# main.net
KiCad netlist of a schematic drawn in EAGLE
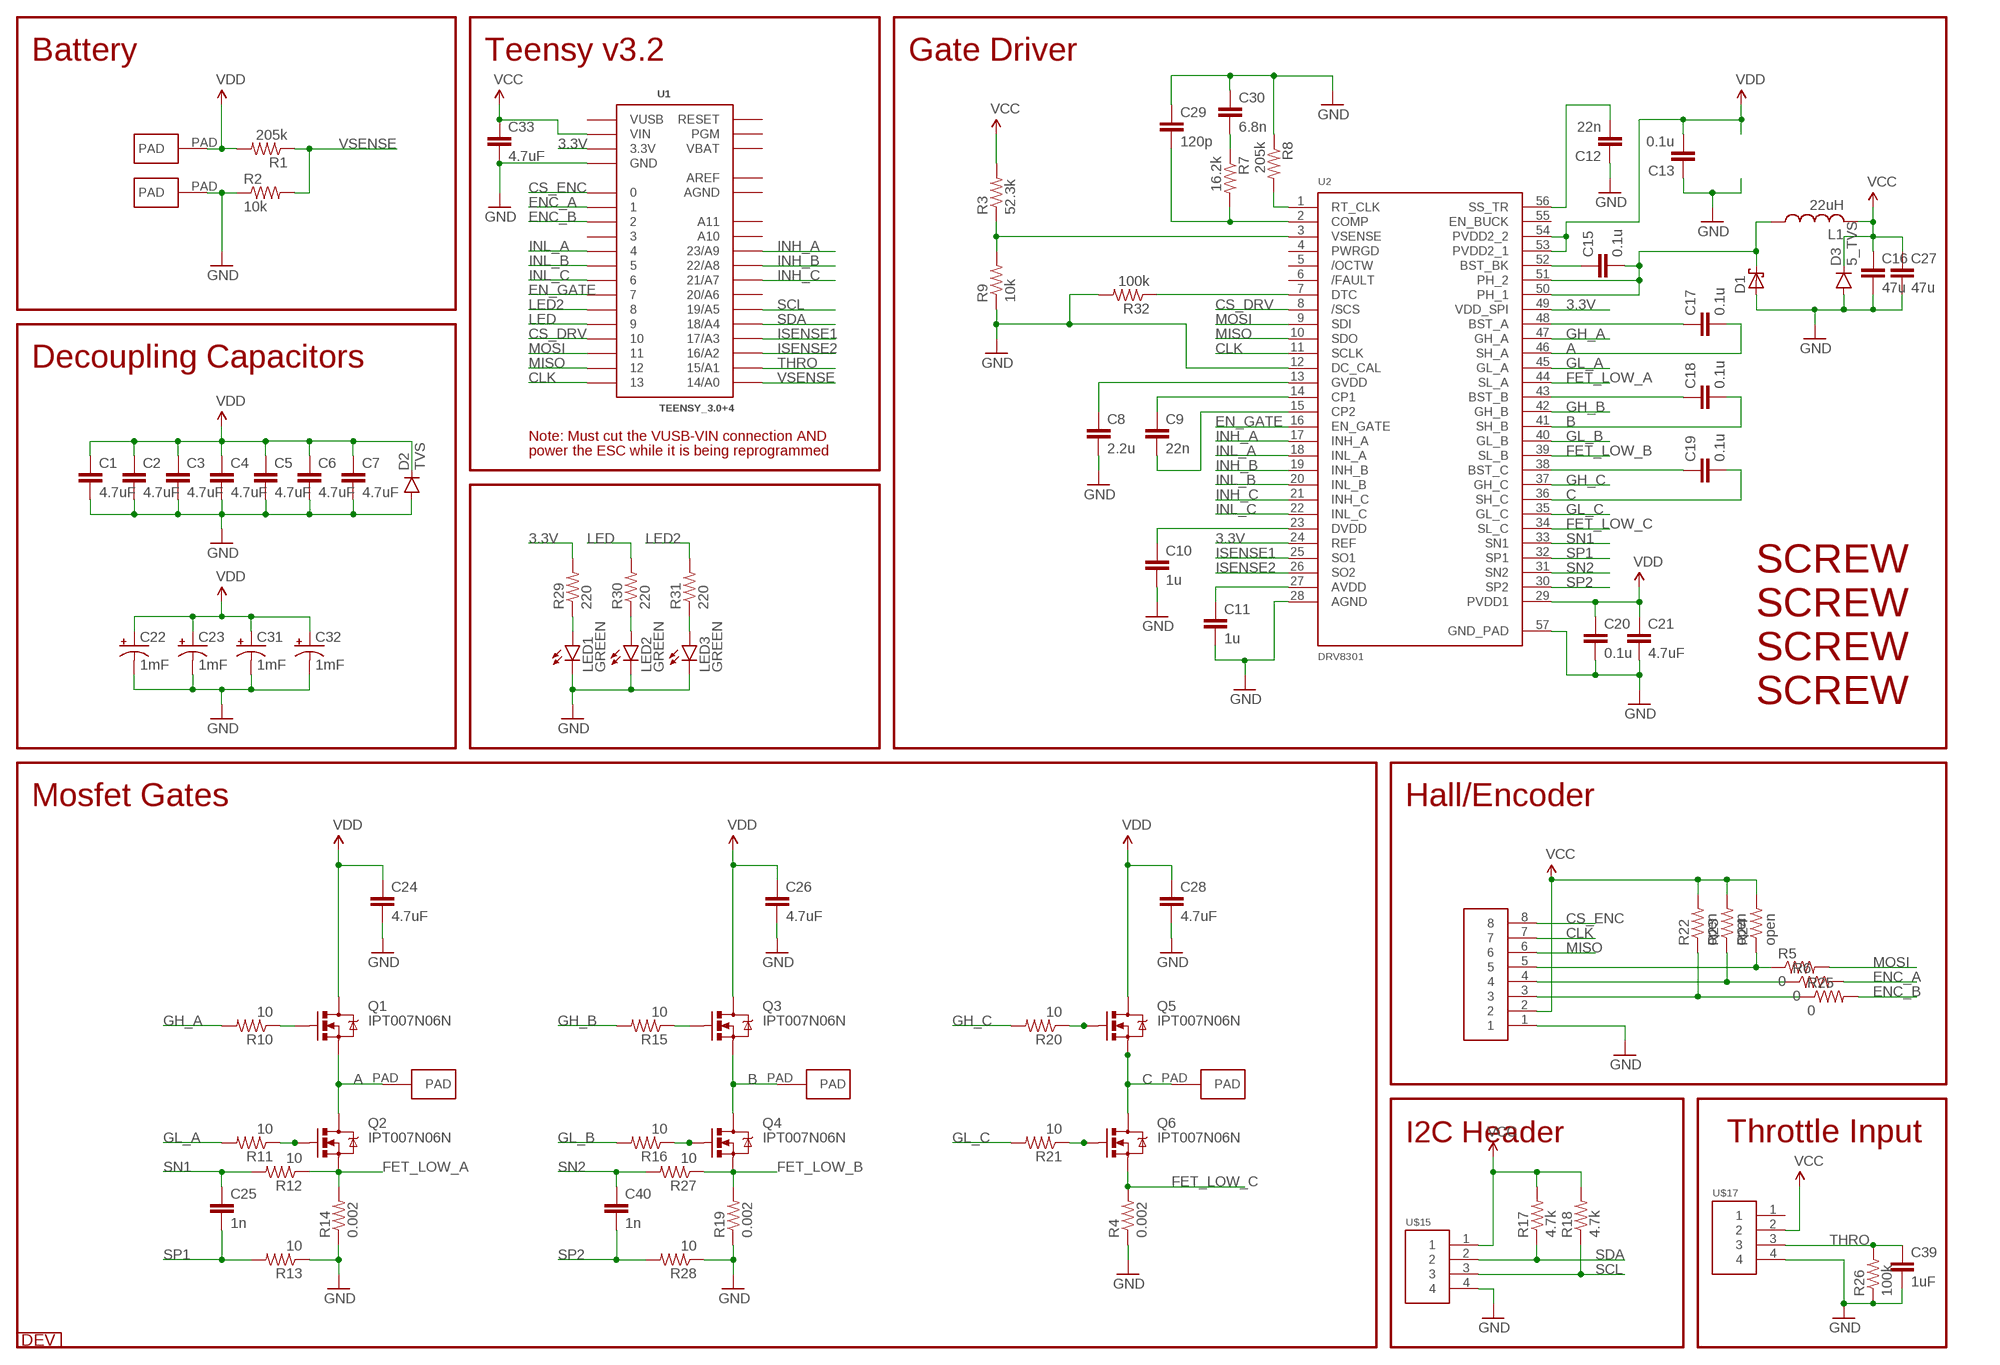
[diagram p0: schematic, sheet 1]

(export (version "E")
  (design (tool "Eeschema 10.0.6"))
  (components
    (comp (ref "C1")
      (value "4.7uF")
      (footprint "eagle-import:1206")
      (libsource (lib "eagle-import") (part "CAP1206"))
    )
    (comp (ref "C2")
      (value "4.7uF")
      (footprint "eagle-import:1206")
      (libsource (lib "eagle-import") (part "CAP1206"))
    )
    (comp (ref "C3")
      (value "4.7uF")
      (footprint "eagle-import:1206")
      (libsource (lib "eagle-import") (part "CAP1206"))
    )
    (comp (ref "C4")
      (value "4.7uF")
      (footprint "eagle-import:1206")
      (libsource (lib "eagle-import") (part "CAP1206"))
    )
    (comp (ref "C5")
      (value "4.7uF")
      (footprint "eagle-import:1206")
      (libsource (lib "eagle-import") (part "CAP1206"))
    )
    (comp (ref "C6")
      (value "4.7uF")
      (footprint "eagle-import:1206")
      (libsource (lib "eagle-import") (part "CAP1206"))
    )
    (comp (ref "C7")
      (value "4.7uF")
      (footprint "eagle-import:1206")
      (libsource (lib "eagle-import") (part "CAP1206"))
    )
    (comp (ref "C8")
      (value "2.2u")
      (footprint "eagle-import:0603-CAP")
      (libsource (lib "eagle-import") (part "CAP0603-CAP"))
    )
    (comp (ref "C9")
      (value "22n")
      (footprint "eagle-import:0603-CAP")
      (libsource (lib "eagle-import") (part "CAP0603-CAP"))
    )
    (comp (ref "C10")
      (value "1u")
      (footprint "eagle-import:0603-CAP")
      (libsource (lib "eagle-import") (part "CAP0603-CAP"))
    )
    (comp (ref "C11")
      (value "1u")
      (footprint "eagle-import:0603-CAP")
      (libsource (lib "eagle-import") (part "CAP0603-CAP"))
    )
    (comp (ref "C12")
      (value "22n")
      (footprint "eagle-import:0603-CAP")
      (libsource (lib "eagle-import") (part "CAP0603-CAP"))
    )
    (comp (ref "C13")
      (value "0.1u")
      (footprint "eagle-import:0603-CAP")
      (libsource (lib "eagle-import") (part "CAP0603-CAP"))
    )
    (comp (ref "C15")
      (value "0.1u")
      (footprint "eagle-import:0603-CAP")
      (libsource (lib "eagle-import") (part "CAP0603-CAP"))
    )
    (comp (ref "C16")
      (value "47u")
      (footprint "eagle-import:0805")
      (libsource (lib "eagle-import") (part "CAP0805"))
    )
    (comp (ref "C17")
      (value "0.1u")
      (footprint "eagle-import:0603-CAP")
      (libsource (lib "eagle-import") (part "CAP0603-CAP"))
    )
    (comp (ref "C18")
      (value "0.1u")
      (footprint "eagle-import:0603-CAP")
      (libsource (lib "eagle-import") (part "CAP0603-CAP"))
    )
    (comp (ref "C19")
      (value "0.1u")
      (footprint "eagle-import:0603-CAP")
      (libsource (lib "eagle-import") (part "CAP0603-CAP"))
    )
    (comp (ref "C20")
      (value "0.1u")
      (footprint "eagle-import:0603-CAP")
      (libsource (lib "eagle-import") (part "CAP0603-CAP"))
    )
    (comp (ref "C21")
      (value "4.7uF")
      (footprint "eagle-import:1206")
      (libsource (lib "eagle-import") (part "CAP1206"))
    )
    (comp (ref "C22")
      (value "1mF")
      (footprint "eagle-import:CPOL-RADIAL-1000UF-25V")
      (libsource (lib "eagle-import") (part "CAP_POLPTH4"))
    )
    (comp (ref "C23")
      (value "1mF")
      (footprint "eagle-import:CPOL-RADIAL-1000UF-25V")
      (libsource (lib "eagle-import") (part "CAP_POLPTH4"))
    )
    (comp (ref "C24")
      (value "4.7uF")
      (footprint "eagle-import:1206")
      (libsource (lib "eagle-import") (part "CAP1206"))
    )
    (comp (ref "C25")
      (value "1n")
      (footprint "eagle-import:0603-CAP")
      (libsource (lib "eagle-import") (part "CAP0603-CAP"))
    )
    (comp (ref "C26")
      (value "4.7uF")
      (footprint "eagle-import:1206")
      (libsource (lib "eagle-import") (part "CAP1206"))
    )
    (comp (ref "C27")
      (value "47u")
      (footprint "eagle-import:0805")
      (libsource (lib "eagle-import") (part "CAP0805"))
    )
    (comp (ref "C28")
      (value "4.7uF")
      (footprint "eagle-import:1206")
      (libsource (lib "eagle-import") (part "CAP1206"))
    )
    (comp (ref "C29")
      (value "120p")
      (footprint "eagle-import:0603-CAP")
      (libsource (lib "eagle-import") (part "CAP0603-CAP"))
    )
    (comp (ref "C30")
      (value "6.8n")
      (footprint "eagle-import:0603-CAP")
      (libsource (lib "eagle-import") (part "CAP0603-CAP"))
    )
    (comp (ref "C31")
      (value "1mF")
      (footprint "eagle-import:CPOL-RADIAL-1000UF-25V")
      (libsource (lib "eagle-import") (part "CAP_POLPTH4"))
    )
    (comp (ref "C32")
      (value "1mF")
      (footprint "eagle-import:CPOL-RADIAL-1000UF-25V")
      (libsource (lib "eagle-import") (part "CAP_POLPTH4"))
    )
    (comp (ref "C33")
      (value "4.7uF")
      (footprint "eagle-import:1206")
      (libsource (lib "eagle-import") (part "CAP1206"))
    )
    (comp (ref "C39")
      (value "1uF")
      (footprint "eagle-import:0603-CAP")
      (libsource (lib "eagle-import") (part "SparkFun-Passives_CAP0603-CAP"))
    )
    (comp (ref "C40")
      (value "1n")
      (footprint "eagle-import:0603-CAP")
      (libsource (lib "eagle-import") (part "CAP0603-CAP"))
    )
    (comp (ref "D1")
      (value "SCHOTTKY_SMA")
      (footprint "eagle-import:SMA")
      (libsource (lib "eagle-import") (part "SCHOTTKY_SMA"))
    )
    (comp (ref "D2")
      (value "TVS")
      (footprint "eagle-import:SMC")
      (libsource (lib "eagle-import") (part "DIODEES3J"))
    )
    (comp (ref "D3")
      (value "5_TVS")
      (footprint "eagle-import:SOT23-3")
      (libsource (lib "eagle-import") (part "DIODESOT23"))
    )
    (comp (ref "L1")
      (value "22uH")
      (footprint "eagle-import:L5650M")
      (libsource (lib "eagle-import") (part "L-USL5650M"))
    )
    (comp (ref "LED1")
      (value "GREEN")
      (footprint "eagle-import:LED-1206")
      (libsource (lib "eagle-import") (part "LED1206"))
    )
    (comp (ref "LED2")
      (value "GREEN")
      (footprint "eagle-import:LED-1206")
      (libsource (lib "eagle-import") (part "LED1206"))
    )
    (comp (ref "LED3")
      (value "GREEN")
      (footprint "eagle-import:LED-1206")
      (libsource (lib "eagle-import") (part "LED1206"))
    )
    (comp (ref "Q1")
      (value "IPT007N06N")
      (footprint "eagle-import:PG-HSOF-8-1")
      (libsource (lib "eagle-import") (part "MOSFET-NCHANNELPG-HSOF-8-1"))
    )
    (comp (ref "Q2")
      (value "IPT007N06N")
      (footprint "eagle-import:PG-HSOF-8-1")
      (libsource (lib "eagle-import") (part "MOSFET-NCHANNELPG-HSOF-8-1"))
    )
    (comp (ref "Q3")
      (value "IPT007N06N")
      (footprint "eagle-import:PG-HSOF-8-1")
      (libsource (lib "eagle-import") (part "MOSFET-NCHANNELPG-HSOF-8-1"))
    )
    (comp (ref "Q4")
      (value "IPT007N06N")
      (footprint "eagle-import:PG-HSOF-8-1")
      (libsource (lib "eagle-import") (part "MOSFET-NCHANNELPG-HSOF-8-1"))
    )
    (comp (ref "Q5")
      (value "IPT007N06N")
      (footprint "eagle-import:PG-HSOF-8-1")
      (libsource (lib "eagle-import") (part "MOSFET-NCHANNELPG-HSOF-8-1"))
    )
    (comp (ref "Q6")
      (value "IPT007N06N")
      (footprint "eagle-import:PG-HSOF-8-1")
      (libsource (lib "eagle-import") (part "MOSFET-NCHANNELPG-HSOF-8-1"))
    )
    (comp (ref "R1")
      (value "205k")
      (footprint "eagle-import:0603-RES")
      (libsource (lib "eagle-import") (part "RESISTOR0603"))
    )
    (comp (ref "R2")
      (value "10k")
      (footprint "eagle-import:0603-RES")
      (libsource (lib "eagle-import") (part "RESISTOR0603"))
    )
    (comp (ref "R3")
      (value "52.3k")
      (footprint "eagle-import:0603-RES")
      (libsource (lib "eagle-import") (part "RESISTOR0603"))
    )
    (comp (ref "R4")
      (value "0.002")
      (footprint "eagle-import:R2512")
      (libsource (lib "eagle-import") (part "SparkFun-Resistors_RESISTOR2512"))
    )
    (comp (ref "R5")
      (value "0")
      (footprint "eagle-import:0603-RES")
      (libsource (lib "eagle-import") (part "RESISTOR0603-RES"))
    )
    (comp (ref "R6")
      (value "0")
      (footprint "eagle-import:0603-RES")
      (libsource (lib "eagle-import") (part "RESISTOR0603-RES"))
    )
    (comp (ref "R7")
      (value "16.2k")
      (footprint "eagle-import:0603-RES")
      (libsource (lib "eagle-import") (part "RESISTOR0603"))
    )
    (comp (ref "R8")
      (value "205k")
      (footprint "eagle-import:0603-RES")
      (libsource (lib "eagle-import") (part "RESISTOR0603"))
    )
    (comp (ref "R9")
      (value "10k")
      (footprint "eagle-import:0603-RES")
      (libsource (lib "eagle-import") (part "RESISTOR0603"))
    )
    (comp (ref "R10")
      (value "10")
      (footprint "eagle-import:0603-RES")
      (libsource (lib "eagle-import") (part "RESISTOR0603"))
    )
    (comp (ref "R11")
      (value "10")
      (footprint "eagle-import:0603-RES")
      (libsource (lib "eagle-import") (part "RESISTOR0603"))
    )
    (comp (ref "R12")
      (value "10")
      (footprint "eagle-import:0603-RES")
      (libsource (lib "eagle-import") (part "RESISTOR0603"))
    )
    (comp (ref "R13")
      (value "10")
      (footprint "eagle-import:0603-RES")
      (libsource (lib "eagle-import") (part "RESISTOR0603"))
    )
    (comp (ref "R14")
      (value "0.002")
      (footprint "eagle-import:R2512")
      (libsource (lib "eagle-import") (part "SparkFun-Resistors_RESISTOR2512"))
    )
    (comp (ref "R15")
      (value "10")
      (footprint "eagle-import:0603-RES")
      (libsource (lib "eagle-import") (part "RESISTOR0603"))
    )
    (comp (ref "R16")
      (value "10")
      (footprint "eagle-import:0603-RES")
      (libsource (lib "eagle-import") (part "RESISTOR0603"))
    )
    (comp (ref "R17")
      (value "4.7k")
      (footprint "eagle-import:0603-RES")
      (libsource (lib "eagle-import") (part "RESISTOR0603-RES"))
    )
    (comp (ref "R18")
      (value "4.7k")
      (footprint "eagle-import:0603-RES")
      (libsource (lib "eagle-import") (part "RESISTOR0603-RES"))
    )
    (comp (ref "R19")
      (value "0.002")
      (footprint "eagle-import:R2512")
      (libsource (lib "eagle-import") (part "SparkFun-Resistors_RESISTOR2512"))
    )
    (comp (ref "R20")
      (value "10")
      (footprint "eagle-import:0603-RES")
      (libsource (lib "eagle-import") (part "RESISTOR0603"))
    )
    (comp (ref "R21")
      (value "10")
      (footprint "eagle-import:0603-RES")
      (libsource (lib "eagle-import") (part "RESISTOR0603"))
    )
    (comp (ref "R22")
      (value "open")
      (footprint "eagle-import:0603-RES")
      (libsource (lib "eagle-import") (part "RESISTOR0603"))
    )
    (comp (ref "R23")
      (value "open")
      (footprint "eagle-import:0603-RES")
      (libsource (lib "eagle-import") (part "RESISTOR0603"))
    )
    (comp (ref "R24")
      (value "open")
      (footprint "eagle-import:0603-RES")
      (libsource (lib "eagle-import") (part "RESISTOR0603"))
    )
    (comp (ref "R25")
      (value "0")
      (footprint "eagle-import:0603-RES")
      (libsource (lib "eagle-import") (part "RESISTOR0603-RES"))
    )
    (comp (ref "R26")
      (value "100k")
      (footprint "eagle-import:0603-RES")
      (libsource (lib "eagle-import") (part "RESISTOR0603-RES"))
    )
    (comp (ref "R27")
      (value "10")
      (footprint "eagle-import:0603-RES")
      (libsource (lib "eagle-import") (part "RESISTOR0603"))
    )
    (comp (ref "R28")
      (value "10")
      (footprint "eagle-import:0603-RES")
      (libsource (lib "eagle-import") (part "RESISTOR0603"))
    )
    (comp (ref "R29")
      (value "220")
      (footprint "eagle-import:0603-RES")
      (libsource (lib "eagle-import") (part "RESISTOR0603"))
    )
    (comp (ref "R30")
      (value "220")
      (footprint "eagle-import:0603-RES")
      (libsource (lib "eagle-import") (part "RESISTOR0603"))
    )
    (comp (ref "R31")
      (value "220")
      (footprint "eagle-import:0603-RES")
      (libsource (lib "eagle-import") (part "RESISTOR0603"))
    )
    (comp (ref "R32")
      (value "100k")
      (footprint "eagle-import:0603-RES")
      (libsource (lib "eagle-import") (part "RESISTOR0603"))
    )
    (comp (ref "U$2")
      (value "HEADER8")
      (footprint "eagle-import:8PINVALULOK")
      (libsource (lib "eagle-import") (part "HEADER8"))
    )
    (comp (ref "U$15")
      (value "HEADER4VALULOK")
      (footprint "eagle-import:4PINVALULOK")
      (libsource (lib "eagle-import") (part "HEADER4VALULOK"))
    )
    (comp (ref "U$16")
      (value "DEV")
      (footprint "eagle-import:DEV")
      (libsource (lib "eagle-import") (part "DEV"))
    )
    (comp (ref "U$17")
      (value "HEADER4VALULOK")
      (footprint "eagle-import:4PINVALULOK")
      (libsource (lib "eagle-import") (part "HEADER4VALULOK"))
    )
    (comp (ref "U$19")
      (value "SCREW")
      (footprint "eagle-import:M3HOLE")
      (libsource (lib "eagle-import") (part "SCREW"))
    )
    (comp (ref "U$20")
      (value "SCREW")
      (footprint "eagle-import:M3HOLE")
      (libsource (lib "eagle-import") (part "SCREW"))
    )
    (comp (ref "U$21")
      (value "SCREW")
      (footprint "eagle-import:M3HOLE")
      (libsource (lib "eagle-import") (part "SCREW"))
    )
    (comp (ref "U$22")
      (value "SCREW")
      (footprint "eagle-import:M3HOLE")
      (libsource (lib "eagle-import") (part "SCREW"))
    )
    (comp (ref "U$23")
      (value "PAD")
      (footprint "eagle-import:PAD")
      (libsource (lib "eagle-import") (part "PAD"))
    )
    (comp (ref "U$24")
      (value "PAD")
      (footprint "eagle-import:PAD")
      (libsource (lib "eagle-import") (part "PAD"))
    )
    (comp (ref "U$25")
      (value "PAD")
      (footprint "eagle-import:PAD")
      (libsource (lib "eagle-import") (part "PAD"))
    )
    (comp (ref "U$26")
      (value "PAD")
      (footprint "eagle-import:PAD")
      (libsource (lib "eagle-import") (part "PAD"))
    )
    (comp (ref "U$27")
      (value "PAD")
      (footprint "eagle-import:PAD")
      (libsource (lib "eagle-import") (part "PAD"))
    )
    (comp (ref "U1")
      (value "TEENSY_3.0+4")
      (footprint "eagle-import:TEENSY_3.0+4")
      (libsource (lib "eagle-import") (part "TEENSY_3.0+4"))
    )
    (comp (ref "U2")
      (value "DRV8301")
      (footprint "eagle-import:DRV8301")
      (libsource (lib "eagle-import") (part "DRV8301"))
    )
  )
  (nets
    (net (code "1") (name "/3.3V") (class "Default")
      (node (ref "R29") (pin "2") (pinfunction "2_2") (pintype "passive"))
      (node (ref "U1") (pin "3.3V") (pinfunction "3.3V_3.3V") (pintype "power_in"))
      (node (ref "U1") (pin "3.3V1") (pinfunction "3.3V_3.3V1") (pintype "power_in"))
      (node (ref "U2") (pin "24") (pinfunction "REF_24") (pintype "bidirectional"))
      (node (ref "U2") (pin "49") (pinfunction "VDD_SPI_49") (pintype "bidirectional"))
    )
    (net (code "2") (name "/A") (class "Default")
      (node (ref "C17") (pin "2") (pinfunction "2_2") (pintype "passive"))
      (node (ref "Q1") (pin "S") (pinfunction "S_S") (pintype "passive"))
      (node (ref "Q2") (pin "D") (pinfunction "D_D") (pintype "passive"))
      (node (ref "U$23") (pin "PAD") (pinfunction "PAD_PAD") (pintype "bidirectional"))
      (node (ref "U2") (pin "46") (pinfunction "SH_A_46") (pintype "bidirectional"))
    )
    (net (code "3") (name "/AGND") (class "Default")
      (node (ref "U1") (pin "AGND") (pinfunction "AGND_AGND") (pintype "power_in"))
    )
    (net (code "4") (name "/AREF") (class "Default")
      (node (ref "U1") (pin "AREF") (pinfunction "AREF_AREF") (pintype "power_in"))
    )
    (net (code "5") (name "/B") (class "Default")
      (node (ref "C18") (pin "2") (pinfunction "2_2") (pintype "passive"))
      (node (ref "Q3") (pin "S") (pinfunction "S_S") (pintype "passive"))
      (node (ref "Q4") (pin "D") (pinfunction "D_D") (pintype "passive"))
      (node (ref "U$24") (pin "PAD") (pinfunction "PAD_PAD") (pintype "bidirectional"))
      (node (ref "U2") (pin "41") (pinfunction "SH_B_41") (pintype "bidirectional"))
    )
    (net (code "6") (name "/C") (class "Default")
      (node (ref "C19") (pin "2") (pinfunction "2_2") (pintype "passive"))
      (node (ref "Q5") (pin "S") (pinfunction "S_S") (pintype "passive"))
      (node (ref "Q6") (pin "D") (pinfunction "D_D") (pintype "passive"))
      (node (ref "U$25") (pin "PAD") (pinfunction "PAD_PAD") (pintype "bidirectional"))
      (node (ref "U2") (pin "36") (pinfunction "SH_C_36") (pintype "bidirectional"))
    )
    (net (code "7") (name "/CLK") (class "Default")
      (node (ref "U$2") (pin "7") (pinfunction "7_7") (pintype "bidirectional"))
      (node (ref "U1") (pin "13") (pinfunction "13_13") (pintype "bidirectional"))
      (node (ref "U2") (pin "11") (pinfunction "SCLK_11") (pintype "bidirectional"))
    )
    (net (code "8") (name "/CS_DRV") (class "Default")
      (node (ref "U1") (pin "10") (pinfunction "10_10") (pintype "bidirectional"))
      (node (ref "U2") (pin "8") (pinfunction "/SCS_8") (pintype "bidirectional"))
    )
    (net (code "9") (name "/CS_ENC") (class "Default")
      (node (ref "U$2") (pin "8") (pinfunction "8_8") (pintype "bidirectional"))
      (node (ref "U1") (pin "0") (pinfunction "0_0") (pintype "bidirectional"))
    )
    (net (code "10") (name "/ENC_A") (class "Default")
      (node (ref "R6") (pin "2") (pinfunction "2_2") (pintype "passive"))
      (node (ref "U1") (pin "1") (pinfunction "1_1") (pintype "bidirectional"))
    )
    (net (code "11") (name "/ENC_B") (class "Default")
      (node (ref "R25") (pin "2") (pinfunction "2_2") (pintype "passive"))
      (node (ref "U1") (pin "2") (pinfunction "2_2") (pintype "bidirectional"))
    )
    (net (code "12") (name "/EN_GATE") (class "Default")
      (node (ref "U1") (pin "7") (pinfunction "7_7") (pintype "bidirectional"))
      (node (ref "U2") (pin "16") (pinfunction "EN_GATE_16") (pintype "bidirectional"))
    )
    (net (code "13") (name "/FET_LOW_A") (class "Default")
      (node (ref "Q2") (pin "S") (pinfunction "S_S") (pintype "passive"))
      (node (ref "R12") (pin "1") (pinfunction "1_1") (pintype "passive"))
      (node (ref "R14") (pin "2") (pinfunction "2_2") (pintype "passive"))
      (node (ref "U2") (pin "44") (pinfunction "SL_A_44") (pintype "bidirectional"))
    )
    (net (code "14") (name "/FET_LOW_B") (class "Default")
      (node (ref "Q4") (pin "S") (pinfunction "S_S") (pintype "passive"))
      (node (ref "R19") (pin "2") (pinfunction "2_2") (pintype "passive"))
      (node (ref "R27") (pin "1") (pinfunction "1_1") (pintype "passive"))
      (node (ref "U2") (pin "39") (pinfunction "SL_B_39") (pintype "bidirectional"))
    )
    (net (code "15") (name "/FET_LOW_C") (class "Default")
      (node (ref "Q6") (pin "S") (pinfunction "S_S") (pintype "passive"))
      (node (ref "R4") (pin "2") (pinfunction "2_2") (pintype "passive"))
      (node (ref "U2") (pin "34") (pinfunction "SL_C_34") (pintype "bidirectional"))
    )
    (net (code "16") (name "/GH_A") (class "Default")
      (node (ref "R10") (pin "2") (pinfunction "2_2") (pintype "passive"))
      (node (ref "U2") (pin "47") (pinfunction "GH_A_47") (pintype "bidirectional"))
    )
    (net (code "17") (name "/GH_B") (class "Default")
      (node (ref "R15") (pin "2") (pinfunction "2_2") (pintype "passive"))
      (node (ref "U2") (pin "42") (pinfunction "GH_B_42") (pintype "bidirectional"))
    )
    (net (code "18") (name "/GH_C") (class "Default")
      (node (ref "R20") (pin "2") (pinfunction "2_2") (pintype "passive"))
      (node (ref "U2") (pin "37") (pinfunction "GH_C_37") (pintype "bidirectional"))
    )
    (net (code "19") (name "/GL_A") (class "Default")
      (node (ref "R11") (pin "2") (pinfunction "2_2") (pintype "passive"))
      (node (ref "U2") (pin "45") (pinfunction "GL_A_45") (pintype "bidirectional"))
    )
    (net (code "20") (name "/GL_B") (class "Default")
      (node (ref "R16") (pin "2") (pinfunction "2_2") (pintype "passive"))
      (node (ref "U2") (pin "40") (pinfunction "GL_B_40") (pintype "bidirectional"))
    )
    (net (code "21") (name "/GL_C") (class "Default")
      (node (ref "R21") (pin "2") (pinfunction "2_2") (pintype "passive"))
      (node (ref "U2") (pin "35") (pinfunction "GL_C_35") (pintype "bidirectional"))
    )
    (net (code "22") (name "/INH_A") (class "Default")
      (node (ref "U1") (pin "23/A9") (pinfunction "23/A9_23/A9") (pintype "bidirectional"))
      (node (ref "U2") (pin "17") (pinfunction "INH_A_17") (pintype "bidirectional"))
    )
    (net (code "23") (name "/INH_B") (class "Default")
      (node (ref "U1") (pin "22/A8") (pinfunction "22/A8_22/A8") (pintype "bidirectional"))
      (node (ref "U2") (pin "19") (pinfunction "INH_B_19") (pintype "bidirectional"))
    )
    (net (code "24") (name "/INH_C") (class "Default")
      (node (ref "U1") (pin "21/A7") (pinfunction "21/A7_21/A7") (pintype "bidirectional"))
      (node (ref "U2") (pin "21") (pinfunction "INH_C_21") (pintype "bidirectional"))
    )
    (net (code "25") (name "/INL_A") (class "Default")
      (node (ref "U1") (pin "4") (pinfunction "4_4") (pintype "bidirectional"))
      (node (ref "U2") (pin "18") (pinfunction "INL_A_18") (pintype "bidirectional"))
    )
    (net (code "26") (name "/INL_B") (class "Default")
      (node (ref "U1") (pin "5") (pinfunction "5_5") (pintype "bidirectional"))
      (node (ref "U2") (pin "20") (pinfunction "INL_B_20") (pintype "bidirectional"))
    )
    (net (code "27") (name "/INL_C") (class "Default")
      (node (ref "U1") (pin "6") (pinfunction "6_6") (pintype "bidirectional"))
      (node (ref "U2") (pin "22") (pinfunction "INL_C_22") (pintype "bidirectional"))
    )
    (net (code "28") (name "/ISENSE1") (class "Default")
      (node (ref "U1") (pin "17/A3") (pinfunction "17/A3_17/A3") (pintype "bidirectional"))
      (node (ref "U2") (pin "25") (pinfunction "SO1_25") (pintype "bidirectional"))
    )
    (net (code "29") (name "/ISENSE2") (class "Default")
      (node (ref "U1") (pin "16/A2") (pinfunction "16/A2_16/A2") (pintype "bidirectional"))
      (node (ref "U2") (pin "26") (pinfunction "SO2_26") (pintype "bidirectional"))
    )
    (net (code "30") (name "/LED") (class "Default")
      (node (ref "R30") (pin "2") (pinfunction "2_2") (pintype "passive"))
      (node (ref "U1") (pin "9") (pinfunction "9_9") (pintype "bidirectional"))
    )
    (net (code "31") (name "/LED2") (class "Default")
      (node (ref "R31") (pin "2") (pinfunction "2_2") (pintype "passive"))
      (node (ref "U1") (pin "8") (pinfunction "8_8") (pintype "bidirectional"))
    )
    (net (code "32") (name "/MISO") (class "Default")
      (node (ref "U$2") (pin "6") (pinfunction "6_6") (pintype "bidirectional"))
      (node (ref "U1") (pin "12") (pinfunction "12_12") (pintype "bidirectional"))
      (node (ref "U2") (pin "10") (pinfunction "SDO_10") (pintype "bidirectional"))
    )
    (net (code "33") (name "/MOSI") (class "Default")
      (node (ref "R5") (pin "2") (pinfunction "2_2") (pintype "passive"))
      (node (ref "U1") (pin "11") (pinfunction "11_11") (pintype "bidirectional"))
      (node (ref "U2") (pin "9") (pinfunction "SDI_9") (pintype "bidirectional"))
    )
    (net (code "34") (name "/SCL") (class "Default")
      (node (ref "R18") (pin "1") (pinfunction "1_1") (pintype "passive"))
      (node (ref "U$15") (pin "3") (pinfunction "3_3") (pintype "bidirectional"))
      (node (ref "U1") (pin "19/A5") (pinfunction "19/A5_19/A5") (pintype "bidirectional"))
    )
    (net (code "35") (name "/SDA") (class "Default")
      (node (ref "R17") (pin "1") (pinfunction "1_1") (pintype "passive"))
      (node (ref "U$15") (pin "2") (pinfunction "2_2") (pintype "bidirectional"))
      (node (ref "U1") (pin "18/A4") (pinfunction "18/A4_18/A4") (pintype "bidirectional"))
    )
    (net (code "36") (name "/SN1") (class "Default")
      (node (ref "C25") (pin "1") (pinfunction "1_1") (pintype "passive"))
      (node (ref "R12") (pin "2") (pinfunction "2_2") (pintype "passive"))
      (node (ref "U2") (pin "33") (pinfunction "SN1_33") (pintype "bidirectional"))
    )
    (net (code "37") (name "/SN2") (class "Default")
      (node (ref "C40") (pin "1") (pinfunction "1_1") (pintype "passive"))
      (node (ref "R27") (pin "2") (pinfunction "2_2") (pintype "passive"))
      (node (ref "U2") (pin "31") (pinfunction "SN2_31") (pintype "bidirectional"))
    )
    (net (code "38") (name "/SP1") (class "Default")
      (node (ref "C25") (pin "2") (pinfunction "2_2") (pintype "passive"))
      (node (ref "R13") (pin "2") (pinfunction "2_2") (pintype "passive"))
      (node (ref "U2") (pin "32") (pinfunction "SP1_32") (pintype "bidirectional"))
    )
    (net (code "39") (name "/SP2") (class "Default")
      (node (ref "C40") (pin "2") (pinfunction "2_2") (pintype "passive"))
      (node (ref "R28") (pin "2") (pinfunction "2_2") (pintype "passive"))
      (node (ref "U2") (pin "30") (pinfunction "SP2_30") (pintype "bidirectional"))
    )
    (net (code "40") (name "/THRO") (class "Default")
      (node (ref "C39") (pin "1") (pinfunction "1_1") (pintype "passive"))
      (node (ref "R26") (pin "2") (pinfunction "2_2") (pintype "passive"))
      (node (ref "U$17") (pin "3") (pinfunction "3_3") (pintype "bidirectional"))
      (node (ref "U1") (pin "15/A1") (pinfunction "15/A1_15/A1") (pintype "bidirectional"))
    )
    (net (code "41") (name "/VBAT") (class "Default")
      (node (ref "U1") (pin "VBAT") (pinfunction "VBAT_VBAT") (pintype "power_in"))
    )
    (net (code "42") (name "/VSENSE") (class "Default")
      (node (ref "R1") (pin "1") (pinfunction "1_1") (pintype "passive"))
      (node (ref "R2") (pin "2") (pinfunction "2_2") (pintype "passive"))
      (node (ref "U1") (pin "14/A0") (pinfunction "14/A0_14/A0") (pintype "bidirectional"))
    )
    (net (code "43") (name "/VUSB") (class "Default")
      (node (ref "U1") (pin "VUSB") (pinfunction "VUSB_VUSB") (pintype "power_in"))
    )
    (net (code "44") (name "GND") (class "Default")
      (node (ref "C1") (pin "2") (pinfunction "2_2") (pintype "passive"))
      (node (ref "C10") (pin "2") (pinfunction "2_2") (pintype "passive"))
      (node (ref "C11") (pin "2") (pinfunction "2_2") (pintype "passive"))
      (node (ref "C12") (pin "1") (pinfunction "1_1") (pintype "passive"))
      (node (ref "C13") (pin "1") (pinfunction "1_1") (pintype "passive"))
      (node (ref "C16") (pin "2") (pinfunction "2_2") (pintype "passive"))
      (node (ref "C2") (pin "2") (pinfunction "2_2") (pintype "passive"))
      (node (ref "C20") (pin "2") (pinfunction "2_2") (pintype "passive"))
      (node (ref "C21") (pin "2") (pinfunction "2_2") (pintype "passive"))
      (node (ref "C22") (pin "-") (pinfunction "-_-") (pintype "passive"))
      (node (ref "C23") (pin "-") (pinfunction "-_-") (pintype "passive"))
      (node (ref "C24") (pin "2") (pinfunction "2_2") (pintype "passive"))
      (node (ref "C26") (pin "2") (pinfunction "2_2") (pintype "passive"))
      (node (ref "C27") (pin "2") (pinfunction "2_2") (pintype "passive"))
      (node (ref "C28") (pin "2") (pinfunction "2_2") (pintype "passive"))
      (node (ref "C29") (pin "1") (pinfunction "1_1") (pintype "passive"))
      (node (ref "C3") (pin "2") (pinfunction "2_2") (pintype "passive"))
      (node (ref "C30") (pin "1") (pinfunction "1_1") (pintype "passive"))
      (node (ref "C31") (pin "-") (pinfunction "-_-") (pintype "passive"))
      (node (ref "C32") (pin "-") (pinfunction "-_-") (pintype "passive"))
      (node (ref "C33") (pin "2") (pinfunction "2_2") (pintype "passive"))
      (node (ref "C39") (pin "2") (pinfunction "2_2") (pintype "passive"))
      (node (ref "C4") (pin "2") (pinfunction "2_2") (pintype "passive"))
      (node (ref "C5") (pin "2") (pinfunction "2_2") (pintype "passive"))
      (node (ref "C6") (pin "2") (pinfunction "2_2") (pintype "passive"))
      (node (ref "C7") (pin "2") (pinfunction "2_2") (pintype "passive"))
      (node (ref "C8") (pin "2") (pinfunction "2_2") (pintype "passive"))
      (node (ref "D1") (pin "A") (pinfunction "A_A") (pintype "passive"))
      (node (ref "D2") (pin "A") (pinfunction "A_A") (pintype "passive"))
      (node (ref "D3") (pin "1") (pinfunction "A_1") (pintype "passive"))
      (node (ref "LED1") (pin "C") (pinfunction "C_C") (pintype "passive"))
      (node (ref "LED2") (pin "C") (pinfunction "C_C") (pintype "passive"))
      (node (ref "LED3") (pin "C") (pinfunction "C_C") (pintype "passive"))
      (node (ref "R13") (pin "1") (pinfunction "1_1") (pintype "passive"))
      (node (ref "R14") (pin "1") (pinfunction "1_1") (pintype "passive"))
      (node (ref "R19") (pin "1") (pinfunction "1_1") (pintype "passive"))
      (node (ref "R2") (pin "1") (pinfunction "1_1") (pintype "passive"))
      (node (ref "R26") (pin "1") (pinfunction "1_1") (pintype "passive"))
      (node (ref "R28") (pin "1") (pinfunction "1_1") (pintype "passive"))
      (node (ref "R32") (pin "2") (pinfunction "2_2") (pintype "passive"))
      (node (ref "R4") (pin "1") (pinfunction "1_1") (pintype "passive"))
      (node (ref "R8") (pin "1") (pinfunction "1_1") (pintype "passive"))
      (node (ref "R9") (pin "1") (pinfunction "1_1") (pintype "passive"))
      (node (ref "U$15") (pin "4") (pinfunction "4_4") (pintype "bidirectional"))
      (node (ref "U$17") (pin "4") (pinfunction "4_4") (pintype "bidirectional"))
      (node (ref "U$2") (pin "1") (pinfunction "1_1") (pintype "bidirectional"))
      (node (ref "U$27") (pin "PAD") (pinfunction "PAD_PAD") (pintype "bidirectional"))
      (node (ref "U1") (pin "GND") (pinfunction "GND_GND") (pintype "power_in"))
      (node (ref "U1") (pin "GND1") (pinfunction "GND_GND1") (pintype "power_in"))
      (node (ref "U2") (pin "12") (pinfunction "DC_CAL_12") (pintype "bidirectional"))
      (node (ref "U2") (pin "28") (pinfunction "AGND_28") (pintype "bidirectional"))
      (node (ref "U2") (pin "57") (pinfunction "GND_PAD_57") (pintype "bidirectional"))
    )
    (net (code "45") (name "Net-(C30-Pad2)") (class "Default")
      (node (ref "C30") (pin "2") (pinfunction "2_2") (pintype "passive"))
      (node (ref "R7") (pin "1") (pinfunction "1_1") (pintype "passive"))
    )
    (net (code "46") (name "Net-(LED1-PadA)") (class "Default")
      (node (ref "LED1") (pin "A") (pinfunction "A_A") (pintype "passive"))
      (node (ref "R29") (pin "1") (pinfunction "1_1") (pintype "passive"))
    )
    (net (code "47") (name "Net-(LED2-PadA)") (class "Default")
      (node (ref "LED2") (pin "A") (pinfunction "A_A") (pintype "passive"))
      (node (ref "R30") (pin "1") (pinfunction "1_1") (pintype "passive"))
    )
    (net (code "48") (name "Net-(LED3-PadA)") (class "Default")
      (node (ref "LED3") (pin "A") (pinfunction "A_A") (pintype "passive"))
      (node (ref "R31") (pin "1") (pinfunction "1_1") (pintype "passive"))
    )
    (net (code "49") (name "Net-(Q1-PadG)") (class "Default")
      (node (ref "Q1") (pin "G") (pinfunction "G_G") (pintype "passive"))
      (node (ref "R10") (pin "1") (pinfunction "1_1") (pintype "passive"))
    )
    (net (code "50") (name "Net-(Q2-PadG)") (class "Default")
      (node (ref "Q2") (pin "G") (pinfunction "G_G") (pintype "passive"))
      (node (ref "R11") (pin "1") (pinfunction "1_1") (pintype "passive"))
    )
    (net (code "51") (name "Net-(Q3-PadG)") (class "Default")
      (node (ref "Q3") (pin "G") (pinfunction "G_G") (pintype "passive"))
      (node (ref "R15") (pin "1") (pinfunction "1_1") (pintype "passive"))
    )
    (net (code "52") (name "Net-(Q4-PadG)") (class "Default")
      (node (ref "Q4") (pin "G") (pinfunction "G_G") (pintype "passive"))
      (node (ref "R16") (pin "1") (pinfunction "1_1") (pintype "passive"))
    )
    (net (code "53") (name "Net-(Q5-PadG)") (class "Default")
      (node (ref "Q5") (pin "G") (pinfunction "G_G") (pintype "passive"))
      (node (ref "R20") (pin "1") (pinfunction "1_1") (pintype "passive"))
    )
    (net (code "54") (name "Net-(Q6-PadG)") (class "Default")
      (node (ref "Q6") (pin "G") (pinfunction "G_G") (pintype "passive"))
      (node (ref "R21") (pin "1") (pinfunction "1_1") (pintype "passive"))
    )
    (net (code "55") (name "Net-(R22-Pad1)") (class "Default")
      (node (ref "R22") (pin "1") (pinfunction "1_1") (pintype "passive"))
      (node (ref "R25") (pin "1") (pinfunction "1_1") (pintype "passive"))
      (node (ref "U$2") (pin "3") (pinfunction "3_3") (pintype "bidirectional"))
    )
    (net (code "56") (name "Net-(R23-Pad1)") (class "Default")
      (node (ref "R23") (pin "1") (pinfunction "1_1") (pintype "passive"))
      (node (ref "R6") (pin "1") (pinfunction "1_1") (pintype "passive"))
      (node (ref "U$2") (pin "4") (pinfunction "4_4") (pintype "bidirectional"))
    )
    (net (code "57") (name "Net-(R24-Pad1)") (class "Default")
      (node (ref "R24") (pin "1") (pinfunction "1_1") (pintype "passive"))
      (node (ref "R5") (pin "1") (pinfunction "1_1") (pintype "passive"))
      (node (ref "U$2") (pin "5") (pinfunction "5_5") (pintype "bidirectional"))
    )
    (net (code "58") (name "Net-(U2-AVDD)") (class "Default")
      (node (ref "C11") (pin "1") (pinfunction "1_1") (pintype "passive"))
      (node (ref "U2") (pin "27") (pinfunction "AVDD_27") (pintype "bidirectional"))
    )
    (net (code "59") (name "Net-(U2-BST_A)") (class "Default")
      (node (ref "C17") (pin "1") (pinfunction "1_1") (pintype "passive"))
      (node (ref "U2") (pin "48") (pinfunction "BST_A_48") (pintype "bidirectional"))
    )
    (net (code "60") (name "Net-(U2-BST_B)") (class "Default")
      (node (ref "C18") (pin "1") (pinfunction "1_1") (pintype "passive"))
      (node (ref "U2") (pin "43") (pinfunction "BST_B_43") (pintype "bidirectional"))
    )
    (net (code "61") (name "Net-(U2-BST_BK)") (class "Default")
      (node (ref "C15") (pin "1") (pinfunction "1_1") (pintype "passive"))
      (node (ref "U2") (pin "52") (pinfunction "BST_BK_52") (pintype "bidirectional"))
    )
    (net (code "62") (name "Net-(U2-BST_C)") (class "Default")
      (node (ref "C19") (pin "1") (pinfunction "1_1") (pintype "passive"))
      (node (ref "U2") (pin "38") (pinfunction "BST_C_38") (pintype "bidirectional"))
    )
    (net (code "63") (name "Net-(U2-COMP)") (class "Default")
      (node (ref "C29") (pin "2") (pinfunction "2_2") (pintype "passive"))
      (node (ref "R7") (pin "2") (pinfunction "2_2") (pintype "passive"))
      (node (ref "U2") (pin "2") (pinfunction "COMP_2") (pintype "bidirectional"))
    )
    (net (code "64") (name "Net-(U2-CP1)") (class "Default")
      (node (ref "C9") (pin "1") (pinfunction "1_1") (pintype "passive"))
      (node (ref "U2") (pin "14") (pinfunction "CP1_14") (pintype "bidirectional"))
    )
    (net (code "65") (name "Net-(U2-CP2)") (class "Default")
      (node (ref "C9") (pin "2") (pinfunction "2_2") (pintype "passive"))
      (node (ref "U2") (pin "15") (pinfunction "CP2_15") (pintype "bidirectional"))
    )
    (net (code "66") (name "Net-(U2-DTC)") (class "Default")
      (node (ref "R32") (pin "1") (pinfunction "1_1") (pintype "passive"))
      (node (ref "U2") (pin "7") (pinfunction "DTC_7") (pintype "bidirectional"))
    )
    (net (code "67") (name "Net-(U2-DVDD)") (class "Default")
      (node (ref "C10") (pin "1") (pinfunction "1_1") (pintype "passive"))
      (node (ref "U2") (pin "23") (pinfunction "DVDD_23") (pintype "bidirectional"))
    )
    (net (code "68") (name "Net-(U2-GVDD)") (class "Default")
      (node (ref "C8") (pin "1") (pinfunction "1_1") (pintype "passive"))
      (node (ref "U2") (pin "13") (pinfunction "GVDD_13") (pintype "bidirectional"))
    )
    (net (code "69") (name "Net-(U2-PH_1)") (class "Default")
      (node (ref "C15") (pin "2") (pinfunction "2_2") (pintype "passive"))
      (node (ref "D1") (pin "C") (pinfunction "C_C") (pintype "passive"))
      (node (ref "L1") (pin "1") (pinfunction "1_1") (pintype "passive"))
      (node (ref "U2") (pin "50") (pinfunction "PH_1_50") (pintype "bidirectional"))
      (node (ref "U2") (pin "51") (pinfunction "PH_2_51") (pintype "bidirectional"))
    )
    (net (code "70") (name "Net-(U2-RT_CLK)") (class "Default")
      (node (ref "R8") (pin "2") (pinfunction "2_2") (pintype "passive"))
      (node (ref "U2") (pin "1") (pinfunction "RT_CLK_1") (pintype "bidirectional"))
    )
    (net (code "71") (name "Net-(U2-SS_TR)") (class "Default")
      (node (ref "C12") (pin "2") (pinfunction "2_2") (pintype "passive"))
      (node (ref "U2") (pin "56") (pinfunction "SS_TR_56") (pintype "bidirectional"))
    )
    (net (code "72") (name "Net-(U2-VSENSE)") (class "Default")
      (node (ref "R3") (pin "1") (pinfunction "1_1") (pintype "passive"))
      (node (ref "R9") (pin "2") (pinfunction "2_2") (pintype "passive"))
      (node (ref "U2") (pin "3") (pinfunction "VSENSE_3") (pintype "bidirectional"))
    )
    (net (code "73") (name "VCC") (class "Default")
      (node (ref "C16") (pin "1") (pinfunction "1_1") (pintype "passive"))
      (node (ref "C27") (pin "1") (pinfunction "1_1") (pintype "passive"))
      (node (ref "C33") (pin "1") (pinfunction "1_1") (pintype "passive"))
      (node (ref "D3") (pin "3") (pinfunction "C_3") (pintype "passive"))
      (node (ref "L1") (pin "2") (pinfunction "2_2") (pintype "passive"))
      (node (ref "R17") (pin "2") (pinfunction "2_2") (pintype "passive"))
      (node (ref "R18") (pin "2") (pinfunction "2_2") (pintype "passive"))
      (node (ref "R22") (pin "2") (pinfunction "2_2") (pintype "passive"))
      (node (ref "R23") (pin "2") (pinfunction "2_2") (pintype "passive"))
      (node (ref "R24") (pin "2") (pinfunction "2_2") (pintype "passive"))
      (node (ref "R3") (pin "2") (pinfunction "2_2") (pintype "passive"))
      (node (ref "U$15") (pin "1") (pinfunction "1_1") (pintype "bidirectional"))
      (node (ref "U$17") (pin "2") (pinfunction "2_2") (pintype "bidirectional"))
      (node (ref "U$2") (pin "2") (pinfunction "2_2") (pintype "bidirectional"))
      (node (ref "U1") (pin "VIN") (pinfunction "VIN_VIN") (pintype "power_in"))
    )
    (net (code "74") (name "VDD") (class "Default")
      (node (ref "C1") (pin "1") (pinfunction "1_1") (pintype "passive"))
      (node (ref "C13") (pin "2") (pinfunction "2_2") (pintype "passive"))
      (node (ref "C2") (pin "1") (pinfunction "1_1") (pintype "passive"))
      (node (ref "C20") (pin "1") (pinfunction "1_1") (pintype "passive"))
      (node (ref "C21") (pin "1") (pinfunction "1_1") (pintype "passive"))
      (node (ref "C22") (pin "+") (pinfunction "+_+") (pintype "passive"))
      (node (ref "C23") (pin "+") (pinfunction "+_+") (pintype "passive"))
      (node (ref "C24") (pin "1") (pinfunction "1_1") (pintype "passive"))
      (node (ref "C26") (pin "1") (pinfunction "1_1") (pintype "passive"))
      (node (ref "C28") (pin "1") (pinfunction "1_1") (pintype "passive"))
      (node (ref "C3") (pin "1") (pinfunction "1_1") (pintype "passive"))
      (node (ref "C31") (pin "+") (pinfunction "+_+") (pintype "passive"))
      (node (ref "C32") (pin "+") (pinfunction "+_+") (pintype "passive"))
      (node (ref "C4") (pin "1") (pinfunction "1_1") (pintype "passive"))
      (node (ref "C5") (pin "1") (pinfunction "1_1") (pintype "passive"))
      (node (ref "C6") (pin "1") (pinfunction "1_1") (pintype "passive"))
      (node (ref "C7") (pin "1") (pinfunction "1_1") (pintype "passive"))
      (node (ref "D2") (pin "C") (pinfunction "C_C") (pintype "passive"))
      (node (ref "Q1") (pin "D") (pinfunction "D_D") (pintype "passive"))
      (node (ref "Q3") (pin "D") (pinfunction "D_D") (pintype "passive"))
      (node (ref "Q5") (pin "D") (pinfunction "D_D") (pintype "passive"))
      (node (ref "R1") (pin "2") (pinfunction "2_2") (pintype "passive"))
      (node (ref "U$26") (pin "PAD") (pinfunction "PAD_PAD") (pintype "bidirectional"))
      (node (ref "U2") (pin "29") (pinfunction "PVDD1_29") (pintype "bidirectional"))
      (node (ref "U2") (pin "53") (pinfunction "PVDD2_1_53") (pintype "bidirectional"))
      (node (ref "U2") (pin "54") (pinfunction "PVDD2_2_54") (pintype "bidirectional"))
    )
    (net (code "75") (name "unconnected-(U$17-Pad1)") (class "Default")
      (node (ref "U$17") (pin "1") (pinfunction "1_1") (pintype "bidirectional"))
    )
    (net (code "76") (name "unconnected-(U1-Pad3)") (class "Default")
      (node (ref "U1") (pin "3") (pinfunction "3_3") (pintype "bidirectional"))
    )
    (net (code "77") (name "unconnected-(U1-Pad20{slash}A6)") (class "Default")
      (node (ref "U1") (pin "20/A6") (pinfunction "20/A6_20/A6") (pintype "bidirectional"))
    )
    (net (code "78") (name "unconnected-(U1-PadA10)") (class "Default")
      (node (ref "U1") (pin "A10") (pinfunction "A10_A10") (pintype "bidirectional"))
    )
    (net (code "79") (name "unconnected-(U1-PadA11)") (class "Default")
      (node (ref "U1") (pin "A11") (pinfunction "A11_A11") (pintype "bidirectional"))
    )
    (net (code "80") (name "unconnected-(U1-PadPGM)") (class "Default")
      (node (ref "U1") (pin "PGM") (pinfunction "PGM_PGM") (pintype "bidirectional"))
    )
    (net (code "81") (name "unconnected-(U1-PadRESET)") (class "Default")
      (node (ref "U1") (pin "RESET") (pinfunction "RESET_RESET") (pintype "bidirectional"))
    )
    (net (code "82") (name "unconnected-(U2-EN_BUCK-Pad55)") (class "Default")
      (node (ref "U2") (pin "55") (pinfunction "EN_BUCK_55") (pintype "bidirectional"))
    )
    (net (code "83") (name "unconnected-(U2-PWRGD-Pad4)") (class "Default")
      (node (ref "U2") (pin "4") (pinfunction "PWRGD_4") (pintype "bidirectional"))
    )
    (net (code "84") (name "unconnected-(U2-{slash}FAULT-Pad6)") (class "Default")
      (node (ref "U2") (pin "6") (pinfunction "/FAULT_6") (pintype "bidirectional"))
    )
    (net (code "85") (name "unconnected-(U2-{slash}OCTW-Pad5)") (class "Default")
      (node (ref "U2") (pin "5") (pinfunction "/OCTW_5") (pintype "bidirectional"))
    )
  )
)
